# extruder_board_--_placement_2.net
KiCad netlist of a schematic drawn in EAGLE
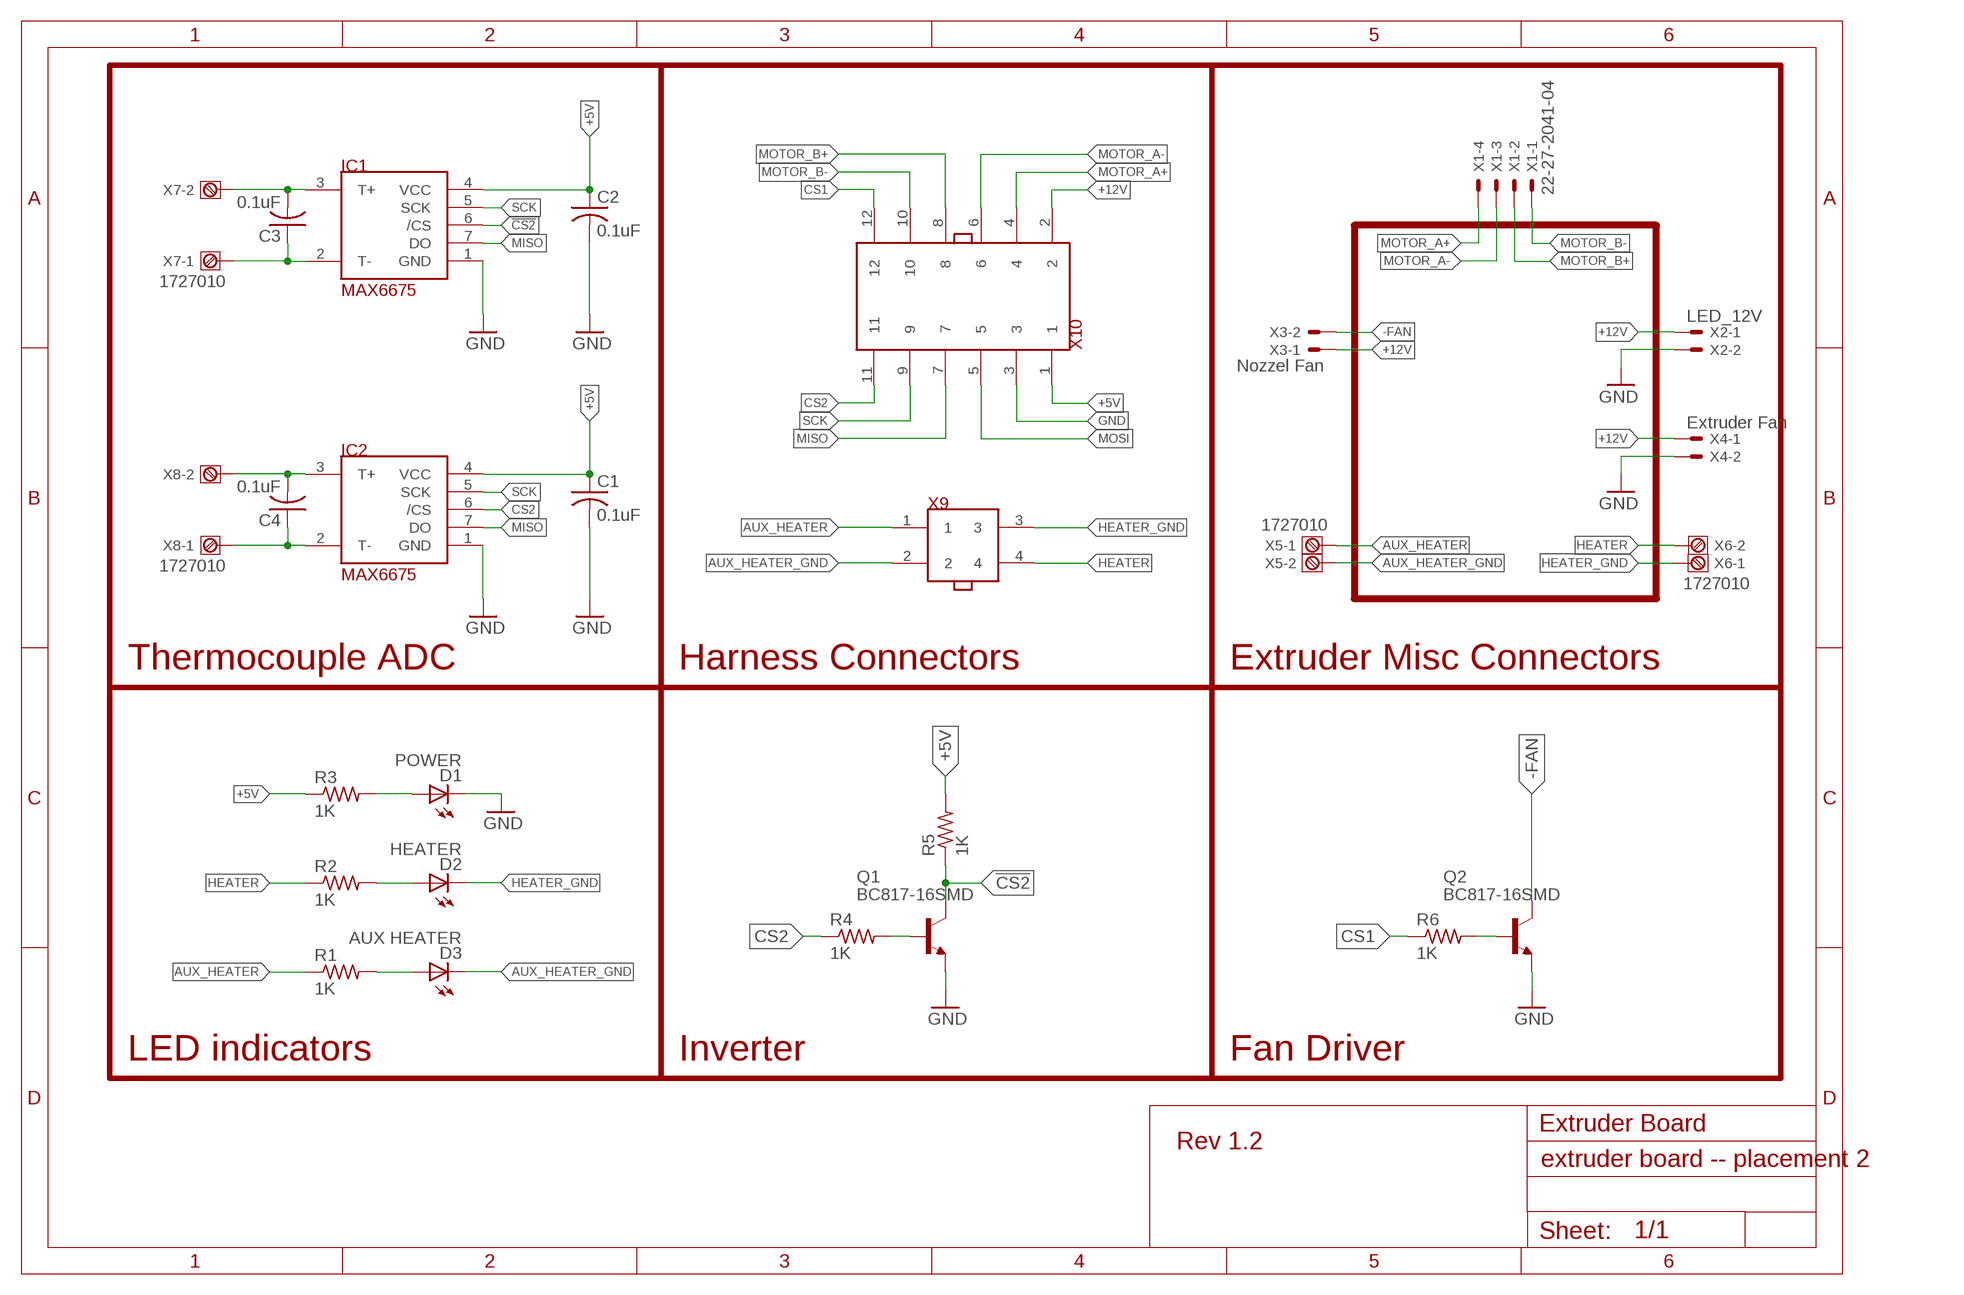
[diagram p0: schematic, sheet 1]

(export (version "E")
  (design (tool "Eeschema 10.0.6"))
  (components
    (comp (ref "C1")
      (value "0.1uF")
      (footprint "eagle-import:C0603K")
      (libsource (lib "eagle-import") (part "C-USC0603K"))
    )
    (comp (ref "C2")
      (value "0.1uF")
      (footprint "eagle-import:C0603K")
      (libsource (lib "eagle-import") (part "C-USC0603K"))
    )
    (comp (ref "C3")
      (value "0.1uF")
      (footprint "eagle-import:C0603K")
      (libsource (lib "eagle-import") (part "C-USC0603K"))
    )
    (comp (ref "C4")
      (value "0.1uF")
      (footprint "eagle-import:C0603K")
      (libsource (lib "eagle-import") (part "C-USC0603K"))
    )
    (comp (ref "D1")
      (value "POWER")
      (footprint "eagle-import:CHIPLED_0805")
      (libsource (lib "eagle-import") (part "LEDCHIPLED_0805"))
    )
    (comp (ref "D2")
      (value "HEATER")
      (footprint "eagle-import:CHIPLED_0805")
      (libsource (lib "eagle-import") (part "LEDCHIPLED_0805"))
    )
    (comp (ref "D3")
      (value "AUX HEATER")
      (footprint "eagle-import:CHIPLED_0805")
      (libsource (lib "eagle-import") (part "LEDCHIPLED_0805"))
    )
    (comp (ref "IC1")
      (value "MAX6675")
      (footprint "eagle-import:SO-8")
      (libsource (lib "eagle-import") (part "MAX6675"))
    )
    (comp (ref "IC2")
      (value "MAX6675")
      (footprint "eagle-import:SO-8")
      (libsource (lib "eagle-import") (part "MAX6675"))
    )
    (comp (ref "Q1")
      (value "BC817-16SMD")
      (footprint "eagle-import:SOT23-BEC")
      (libsource (lib "eagle-import") (part "BC817SMD-16"))
    )
    (comp (ref "Q2")
      (value "BC817-16SMD")
      (footprint "eagle-import:SOT23-BEC")
      (libsource (lib "eagle-import") (part "BC817SMD-16"))
    )
    (comp (ref "R1")
      (value "1K")
      (footprint "eagle-import:R0603")
      (libsource (lib "eagle-import") (part "R-US_R0603"))
    )
    (comp (ref "R2")
      (value "1K")
      (footprint "eagle-import:R0603")
      (libsource (lib "eagle-import") (part "R-US_R0603"))
    )
    (comp (ref "R3")
      (value "1K")
      (footprint "eagle-import:R0603")
      (libsource (lib "eagle-import") (part "R-US_R0603"))
    )
    (comp (ref "R4")
      (value "1K")
      (footprint "eagle-import:R0603")
      (libsource (lib "eagle-import") (part "R-US_R0603"))
    )
    (comp (ref "R5")
      (value "1K")
      (footprint "eagle-import:R0603")
      (libsource (lib "eagle-import") (part "R-US_R0603"))
    )
    (comp (ref "R6")
      (value "1K")
      (footprint "eagle-import:R0603")
      (libsource (lib "eagle-import") (part "R-US_R0603"))
    )
    (comp (ref "X1")
      (value "22-27-2041-04")
      (footprint "eagle-import:6410-04")
      (fields (field (name "OC_FARNELL") "unknown") (field (name "OC_NEWARK") "unknown"))
      (libsource (lib "eagle-import") (part "22-?-0427-2041"))
    )
    (comp (ref "X2")
      (value "LED_12V")
      (footprint "eagle-import:6410-02")
      (fields (field (name "OC_FARNELL") "unknown") (field (name "OC_NEWARK") "unknown"))
      (libsource (lib "eagle-import") (part "22-?-0227-2021"))
    )
    (comp (ref "X3")
      (value "Nozzel Fan")
      (footprint "eagle-import:6410-02")
      (fields (field (name "OC_FARNELL") "unknown") (field (name "OC_NEWARK") "unknown"))
      (libsource (lib "eagle-import") (part "22-?-0227-2021"))
    )
    (comp (ref "X4")
      (value "Extruder Fan")
      (footprint "eagle-import:6410-02")
      (fields (field (name "OC_FARNELL") "unknown") (field (name "OC_NEWARK") "unknown"))
      (libsource (lib "eagle-import") (part "22-?-0227-2021"))
    )
    (comp (ref "X5")
      (value "1727010")
      (footprint "eagle-import:1727010")
      (libsource (lib "eagle-import") (part "1727010"))
    )
    (comp (ref "X6")
      (value "1727010")
      (footprint "eagle-import:1727010")
      (libsource (lib "eagle-import") (part "1727010"))
    )
    (comp (ref "X7")
      (value "1727010")
      (footprint "eagle-import:1727010")
      (libsource (lib "eagle-import") (part "1727010"))
    )
    (comp (ref "X8")
      (value "1727010")
      (footprint "eagle-import:1727010")
      (libsource (lib "eagle-import") (part "1727010"))
    )
    (comp (ref "X9")
      (value "5557-04")
      (footprint "eagle-import:5557-04")
      (libsource (lib "eagle-import") (part "5557-04"))
    )
    (comp (ref "X10")
      (value "5557-12")
      (footprint "eagle-import:5557-12")
      (libsource (lib "eagle-import") (part "5557-12"))
    )
  )
  (nets
    (net (code "1") (name "+5V") (class "Default")
      (node (ref "C1") (pin "1") (pinfunction "1_1") (pintype "passive"))
      (node (ref "C2") (pin "1") (pinfunction "1_1") (pintype "passive"))
      (node (ref "IC1") (pin "4") (pinfunction "VCC_4") (pintype "bidirectional"))
      (node (ref "IC2") (pin "4") (pinfunction "VCC_4") (pintype "bidirectional"))
      (node (ref "R3") (pin "1") (pinfunction "1_1") (pintype "passive"))
      (node (ref "R5") (pin "2") (pinfunction "2_2") (pintype "passive"))
      (node (ref "X10") (pin "1") (pinfunction "1_1") (pintype "bidirectional"))
    )
    (net (code "2") (name "+12V") (class "Default")
      (node (ref "X10") (pin "2") (pinfunction "2_2") (pintype "bidirectional"))
      (node (ref "X2") (pin "1") (pinfunction "S_1") (pintype "passive"))
      (node (ref "X3") (pin "1") (pinfunction "S_1") (pintype "passive"))
      (node (ref "X4") (pin "1") (pinfunction "S_1") (pintype "passive"))
    )
    (net (code "3") (name "-FAN") (class "Default")
      (node (ref "Q2") (pin "C") (pinfunction "C_C") (pintype "passive"))
      (node (ref "X3") (pin "2") (pinfunction "S_2") (pintype "passive"))
    )
    (net (code "4") (name "/~{CS2}") (class "Default")
      (node (ref "IC1") (pin "6") (pinfunction "/CS_6") (pintype "bidirectional"))
      (node (ref "Q1") (pin "C") (pinfunction "C_C") (pintype "passive"))
      (node (ref "R5") (pin "1") (pinfunction "1_1") (pintype "passive"))
    )
    (net (code "5") (name "AUX_HEATER") (class "Default")
      (node (ref "R1") (pin "1") (pinfunction "1_1") (pintype "passive"))
      (node (ref "X5") (pin "1") (pinfunction "1_1") (pintype "passive"))
      (node (ref "X9") (pin "1") (pinfunction "1_1") (pintype "bidirectional"))
    )
    (net (code "6") (name "AUX_HEATER_GND") (class "Default")
      (node (ref "D3") (pin "C") (pinfunction "C_C") (pintype "passive"))
      (node (ref "X5") (pin "2") (pinfunction "1_2") (pintype "passive"))
      (node (ref "X9") (pin "2") (pinfunction "2_2") (pintype "bidirectional"))
    )
    (net (code "7") (name "CS1") (class "Default")
      (node (ref "R6") (pin "1") (pinfunction "1_1") (pintype "passive"))
      (node (ref "X10") (pin "12") (pinfunction "12_12") (pintype "bidirectional"))
    )
    (net (code "8") (name "CS2") (class "Default")
      (node (ref "IC2") (pin "6") (pinfunction "/CS_6") (pintype "bidirectional"))
      (node (ref "R4") (pin "1") (pinfunction "1_1") (pintype "passive"))
      (node (ref "X10") (pin "11") (pinfunction "11_11") (pintype "bidirectional"))
    )
    (net (code "9") (name "GND") (class "Default")
      (node (ref "C1") (pin "2") (pinfunction "2_2") (pintype "passive"))
      (node (ref "C2") (pin "2") (pinfunction "2_2") (pintype "passive"))
      (node (ref "D1") (pin "C") (pinfunction "C_C") (pintype "passive"))
      (node (ref "IC1") (pin "1") (pinfunction "GND_1") (pintype "bidirectional"))
      (node (ref "IC2") (pin "1") (pinfunction "GND_1") (pintype "bidirectional"))
      (node (ref "Q1") (pin "E") (pinfunction "E_E") (pintype "passive"))
      (node (ref "Q2") (pin "E") (pinfunction "E_E") (pintype "passive"))
      (node (ref "X10") (pin "3") (pinfunction "3_3") (pintype "bidirectional"))
      (node (ref "X2") (pin "2") (pinfunction "S_2") (pintype "passive"))
      (node (ref "X4") (pin "2") (pinfunction "S_2") (pintype "passive"))
    )
    (net (code "10") (name "HEATER") (class "Default")
      (node (ref "R2") (pin "1") (pinfunction "1_1") (pintype "passive"))
      (node (ref "X6") (pin "2") (pinfunction "1_2") (pintype "passive"))
      (node (ref "X9") (pin "4") (pinfunction "4_4") (pintype "bidirectional"))
    )
    (net (code "11") (name "HEATER_GND") (class "Default")
      (node (ref "D2") (pin "C") (pinfunction "C_C") (pintype "passive"))
      (node (ref "X6") (pin "1") (pinfunction "1_1") (pintype "passive"))
      (node (ref "X9") (pin "3") (pinfunction "3_3") (pintype "bidirectional"))
    )
    (net (code "12") (name "MISO") (class "Default")
      (node (ref "IC1") (pin "7") (pinfunction "DO_7") (pintype "bidirectional"))
      (node (ref "IC2") (pin "7") (pinfunction "DO_7") (pintype "bidirectional"))
      (node (ref "X10") (pin "7") (pinfunction "7_7") (pintype "bidirectional"))
    )
    (net (code "13") (name "MOSI") (class "Default")
      (node (ref "X10") (pin "5") (pinfunction "5_5") (pintype "bidirectional"))
    )
    (net (code "14") (name "MOTOR_A+") (class "Default")
      (node (ref "X1") (pin "4") (pinfunction "S_4") (pintype "passive"))
      (node (ref "X10") (pin "4") (pinfunction "4_4") (pintype "bidirectional"))
    )
    (net (code "15") (name "MOTOR_A-") (class "Default")
      (node (ref "X1") (pin "3") (pinfunction "S_3") (pintype "passive"))
      (node (ref "X10") (pin "6") (pinfunction "6_6") (pintype "bidirectional"))
    )
    (net (code "16") (name "MOTOR_B+") (class "Default")
      (node (ref "X1") (pin "2") (pinfunction "S_2") (pintype "passive"))
      (node (ref "X10") (pin "8") (pinfunction "8_8") (pintype "bidirectional"))
    )
    (net (code "17") (name "MOTOR_B-") (class "Default")
      (node (ref "X1") (pin "1") (pinfunction "S_1") (pintype "passive"))
      (node (ref "X10") (pin "10") (pinfunction "10_10") (pintype "bidirectional"))
    )
    (net (code "18") (name "Net-(D1-PadA)") (class "Default")
      (node (ref "D1") (pin "A") (pinfunction "A_A") (pintype "passive"))
      (node (ref "R3") (pin "2") (pinfunction "2_2") (pintype "passive"))
    )
    (net (code "19") (name "Net-(D2-PadA)") (class "Default")
      (node (ref "D2") (pin "A") (pinfunction "A_A") (pintype "passive"))
      (node (ref "R2") (pin "2") (pinfunction "2_2") (pintype "passive"))
    )
    (net (code "20") (name "Net-(D3-PadA)") (class "Default")
      (node (ref "D3") (pin "A") (pinfunction "A_A") (pintype "passive"))
      (node (ref "R1") (pin "2") (pinfunction "2_2") (pintype "passive"))
    )
    (net (code "21") (name "Net-(IC1-T+)") (class "Default")
      (node (ref "C3") (pin "2") (pinfunction "2_2") (pintype "passive"))
      (node (ref "IC1") (pin "3") (pinfunction "T+_3") (pintype "bidirectional"))
      (node (ref "X7") (pin "2") (pinfunction "1_2") (pintype "passive"))
    )
    (net (code "22") (name "Net-(IC1-T-)") (class "Default")
      (node (ref "C3") (pin "1") (pinfunction "1_1") (pintype "passive"))
      (node (ref "IC1") (pin "2") (pinfunction "T-_2") (pintype "bidirectional"))
      (node (ref "X7") (pin "1") (pinfunction "1_1") (pintype "passive"))
    )
    (net (code "23") (name "Net-(IC2-T+)") (class "Default")
      (node (ref "C4") (pin "2") (pinfunction "2_2") (pintype "passive"))
      (node (ref "IC2") (pin "3") (pinfunction "T+_3") (pintype "bidirectional"))
      (node (ref "X8") (pin "2") (pinfunction "1_2") (pintype "passive"))
    )
    (net (code "24") (name "Net-(IC2-T-)") (class "Default")
      (node (ref "C4") (pin "1") (pinfunction "1_1") (pintype "passive"))
      (node (ref "IC2") (pin "2") (pinfunction "T-_2") (pintype "bidirectional"))
      (node (ref "X8") (pin "1") (pinfunction "1_1") (pintype "passive"))
    )
    (net (code "25") (name "Net-(Q1-PadB)") (class "Default")
      (node (ref "Q1") (pin "B") (pinfunction "B_B") (pintype "passive"))
      (node (ref "R4") (pin "2") (pinfunction "2_2") (pintype "passive"))
    )
    (net (code "26") (name "Net-(Q2-PadB)") (class "Default")
      (node (ref "Q2") (pin "B") (pinfunction "B_B") (pintype "passive"))
      (node (ref "R6") (pin "2") (pinfunction "2_2") (pintype "passive"))
    )
    (net (code "27") (name "SCK") (class "Default")
      (node (ref "IC1") (pin "5") (pinfunction "SCK_5") (pintype "bidirectional"))
      (node (ref "IC2") (pin "5") (pinfunction "SCK_5") (pintype "bidirectional"))
      (node (ref "X10") (pin "9") (pinfunction "9_9") (pintype "bidirectional"))
    )
  )
)
